# 4_DIGITAL.net
KiCad netlist of a schematic drawn in Altium Designer
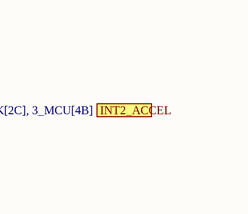
[diagram p0: 4_DIGITAL.SchDoc, left]
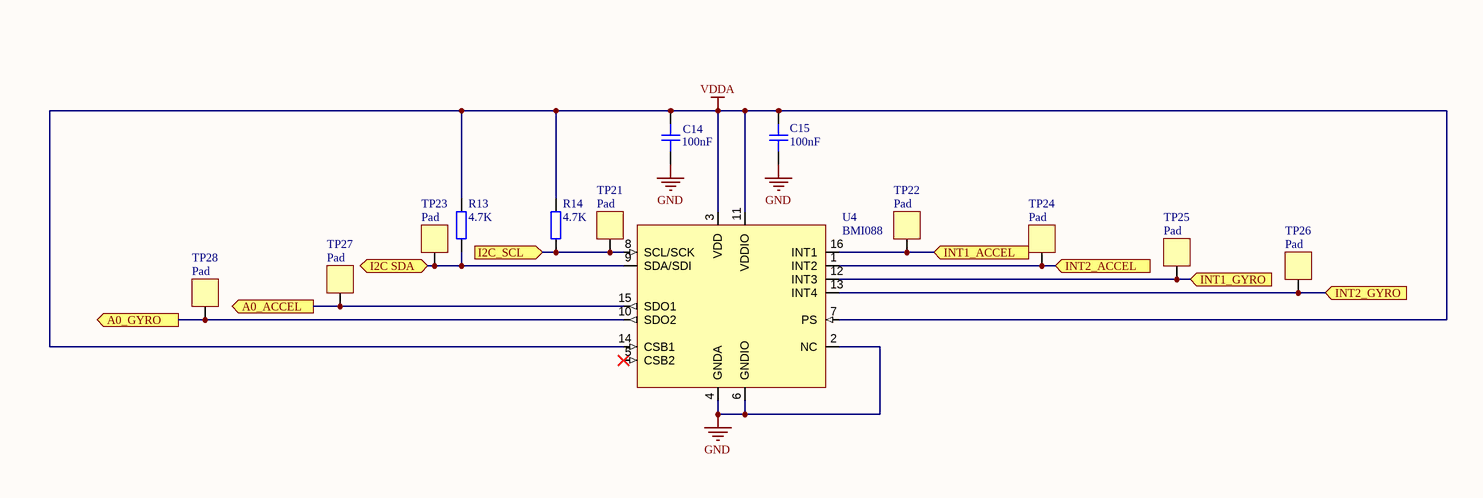
[diagram p1: 4_DIGITAL.SchDoc, right]

(export (version "E")
  (design (tool "Eeschema 10.0.6"))
  (components
    (comp (ref "C14")
      (value "100nF")
      (footprint "CAP_0603")
      (description "Capacitor SMD 0603 16V")
      (libsource (lib "Schematic-Lib-PhilsLab") (part "CAP_0603_16V"))
    )
    (comp (ref "C15")
      (value "100nF")
      (footprint "CAP_0603")
      (description "Capacitor SMD 0603 16V")
      (libsource (lib "Schematic-Lib-PhilsLab") (part "CAP_0603_16V"))
    )
    (comp (ref "R13")
      (value "4.7K")
      (footprint "RES_0603")
      (description "Resistor SMD 0603")
      (libsource (lib "Schematic-Lib-PhilsLab") (part "RES_0603"))
    )
    (comp (ref "R14")
      (value "4.7K")
      (footprint "RES_0603")
      (description "Resistor SMD 0603")
      (libsource (lib "Schematic-Lib-PhilsLab") (part "RES_0603"))
    )
    (comp (ref "TP21")
      (value "Pad")
      (footprint "PAD_SQ_2MM")
      (description "Test Point Square 2mm")
      (libsource (lib "Schematic-Lib-PhilsLab") (part "PAD_SQ_2MM"))
    )
    (comp (ref "TP22")
      (value "Pad")
      (footprint "PAD_SQ_2MM")
      (description "Test Point Square 2mm")
      (libsource (lib "Schematic-Lib-PhilsLab") (part "PAD_SQ_2MM"))
    )
    (comp (ref "TP23")
      (value "Pad")
      (footprint "PAD_SQ_2MM")
      (description "Test Point Square 2mm")
      (libsource (lib "Schematic-Lib-PhilsLab") (part "PAD_SQ_2MM"))
    )
    (comp (ref "TP24")
      (value "Pad")
      (footprint "PAD_SQ_2MM")
      (description "Test Point Square 2mm")
      (libsource (lib "Schematic-Lib-PhilsLab") (part "PAD_SQ_2MM"))
    )
    (comp (ref "TP25")
      (value "Pad")
      (footprint "PAD_SQ_2MM")
      (description "Test Point Square 2mm")
      (libsource (lib "Schematic-Lib-PhilsLab") (part "PAD_SQ_2MM"))
    )
    (comp (ref "TP26")
      (value "Pad")
      (footprint "PAD_SQ_2MM")
      (description "Test Point Square 2mm")
      (libsource (lib "Schematic-Lib-PhilsLab") (part "PAD_SQ_2MM"))
    )
    (comp (ref "TP27")
      (value "Pad")
      (footprint "PAD_SQ_2MM")
      (description "Test Point Square 2mm")
      (libsource (lib "Schematic-Lib-PhilsLab") (part "PAD_SQ_2MM"))
    )
    (comp (ref "TP28")
      (value "Pad")
      (footprint "PAD_SQ_2MM")
      (description "Test Point Square 2mm")
      (libsource (lib "Schematic-Lib-PhilsLab") (part "PAD_SQ_2MM"))
    )
    (comp (ref "U4")
      (value "BMI088")
      (footprint "BMI088")
      (description "Inertial Measurement Unit IMU 6-Axis LGA")
      (fields (field (name "MANUFACTURER") "Bosch"))
      (libsource (lib "Schematic-Lib-PhilsLab") (part "BMI088"))
    )
  )
  (nets
    (net (code "1") (name "/A0_ACCEL") (class "Default")
      (node (ref "TP27") (pin "1") (pinfunction "1_1") (pintype "passive"))
      (node (ref "U4") (pin "15") (pinfunction "SDO1_15") (pintype "output"))
    )
    (net (code "2") (name "/A0_GYRO") (class "Default")
      (node (ref "TP28") (pin "1") (pinfunction "1_1") (pintype "passive"))
      (node (ref "U4") (pin "10") (pinfunction "SDO2_10") (pintype "output"))
    )
    (net (code "3") (name "/I2C SDA") (class "Default")
      (node (ref "R13") (pin "1") (pinfunction "1_1") (pintype "passive"))
      (node (ref "TP23") (pin "1") (pinfunction "1_1") (pintype "passive"))
      (node (ref "U4") (pin "9") (pinfunction "SDA/SDI_9") (pintype "bidirectional"))
    )
    (net (code "4") (name "/I2C_SCL") (class "Default")
      (node (ref "R14") (pin "1") (pinfunction "1_1") (pintype "passive"))
      (node (ref "TP21") (pin "1") (pinfunction "1_1") (pintype "passive"))
      (node (ref "U4") (pin "8") (pinfunction "SCL/SCK_8") (pintype "input"))
    )
    (net (code "5") (name "/INT1_ACCEL") (class "Default")
      (node (ref "TP22") (pin "1") (pinfunction "1_1") (pintype "passive"))
      (node (ref "U4") (pin "16") (pinfunction "INT1_16") (pintype "bidirectional"))
    )
    (net (code "6") (name "/INT1_GYRO") (class "Default")
      (node (ref "TP25") (pin "1") (pinfunction "1_1") (pintype "passive"))
      (node (ref "U4") (pin "12") (pinfunction "INT3_12") (pintype "bidirectional"))
    )
    (net (code "7") (name "/INT2_ACCEL") (class "Default")
      (node (ref "TP24") (pin "1") (pinfunction "1_1") (pintype "passive"))
      (node (ref "U4") (pin "1") (pinfunction "INT2_1") (pintype "bidirectional"))
    )
    (net (code "8") (name "/INT2_GYRO") (class "Default")
      (node (ref "TP26") (pin "1") (pinfunction "1_1") (pintype "passive"))
      (node (ref "U4") (pin "13") (pinfunction "INT4_13") (pintype "bidirectional"))
    )
    (net (code "9") (name "GND") (class "Default")
      (node (ref "C14") (pin "1") (pinfunction "1_1") (pintype "passive"))
      (node (ref "C15") (pin "1") (pinfunction "1_1") (pintype "passive"))
      (node (ref "U4") (pin "2") (pinfunction "NC_2") (pintype "passive"))
      (node (ref "U4") (pin "4") (pinfunction "GNDA_4") (pintype "power_in"))
      (node (ref "U4") (pin "6") (pinfunction "GNDIO_6") (pintype "power_in"))
    )
    (net (code "10") (name "VDDA") (class "Default")
      (node (ref "C14") (pin "2") (pinfunction "2_2") (pintype "passive"))
      (node (ref "C15") (pin "2") (pinfunction "2_2") (pintype "passive"))
      (node (ref "R13") (pin "2") (pinfunction "2_2") (pintype "passive"))
      (node (ref "R14") (pin "2") (pinfunction "2_2") (pintype "passive"))
      (node (ref "U4") (pin "11") (pinfunction "VDDIO_11") (pintype "power_in"))
      (node (ref "U4") (pin "14") (pinfunction "CSB1_14") (pintype "input"))
      (node (ref "U4") (pin "3") (pinfunction "VDD_3") (pintype "power_in"))
      (node (ref "U4") (pin "7") (pinfunction "PS_7") (pintype "input"))
    )
    (net (code "11") (name "unconnected-(U4-CSB2-Pad5)") (class "Default")
      (node (ref "U4") (pin "5") (pinfunction "CSB2_5") (pintype "input+no_connect"))
    )
  )
)
